# PICkit_2.net
KiCad netlist of a schematic drawn in Altium Designer
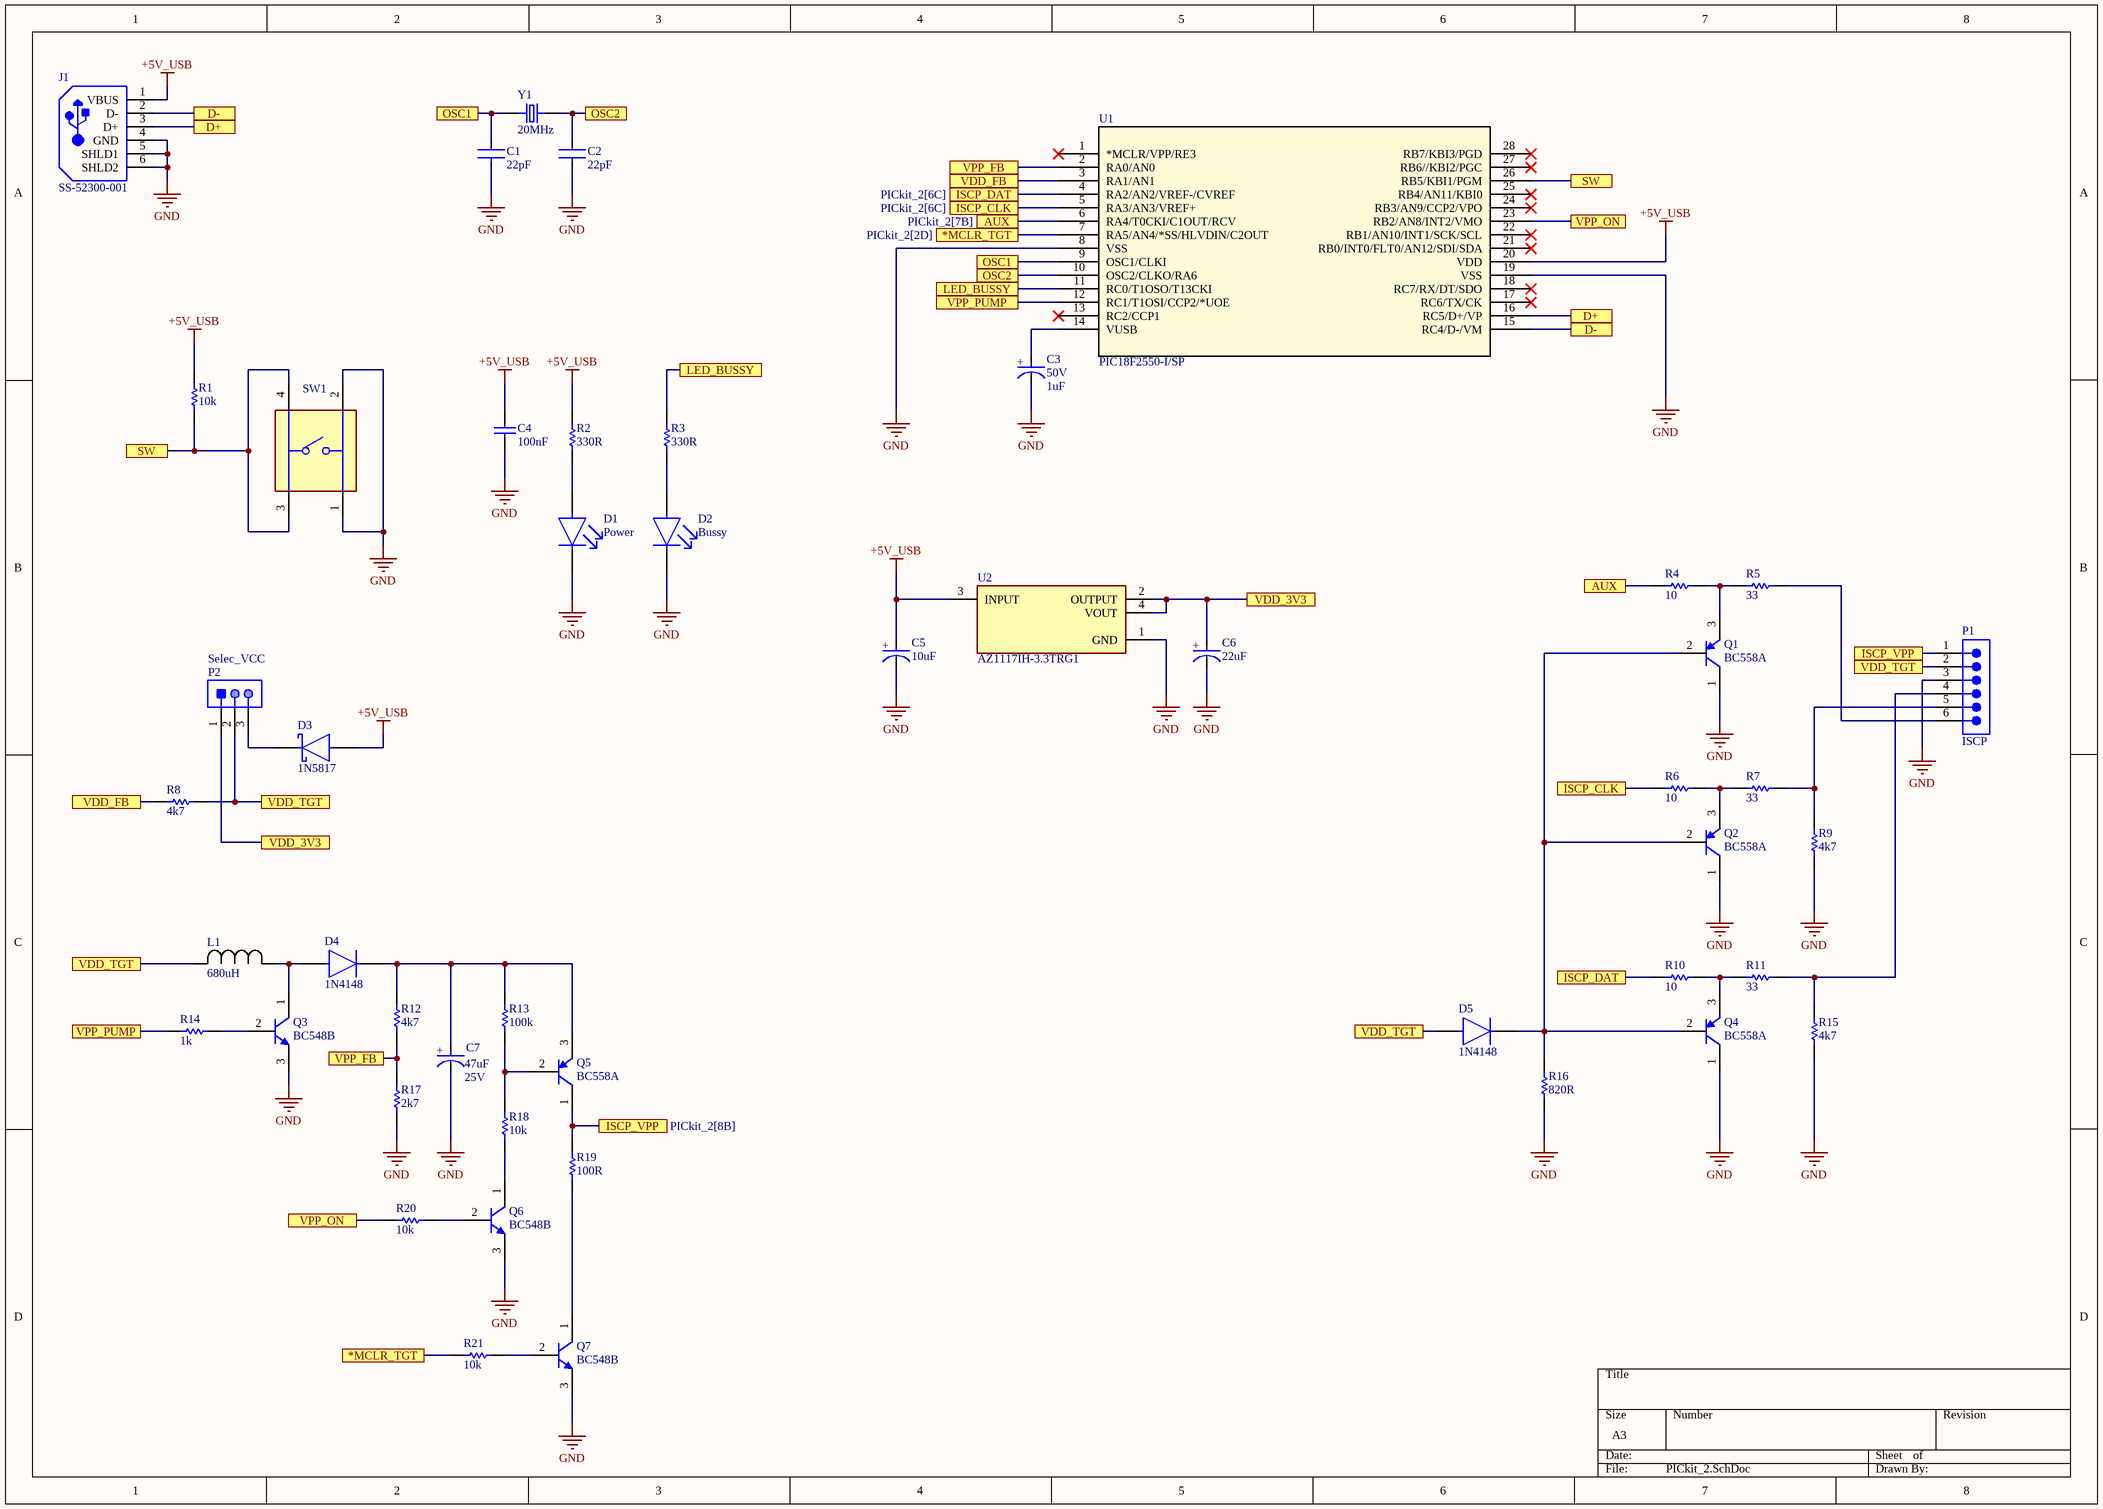
[diagram p0: PICkit_2.SchDoc]

(export (version "E")
  (design (tool "Eeschema 10.0.6"))
  (components
    (comp (ref "C1")
      (value "RCE5C1H220J0K1H03B")
      (footprint "FP-RCE0K1-MFG")
      (description "Cap Ceramic 22pF 50V C0G ±5% Radial 5mm +125°C Automotive Bulk")
      (fields
        (field (name "TOLERANCE") "5%")
        (field (name "CAPACITANCE") "22pF")
        (field (name "MANUFACTURER") "Murata")
      )
      (libsource (lib "Altium Content Vault") (part "b4654b650e69147ec39a6b967a45e02"))
    )
    (comp (ref "C2")
      (value "RCE5C1H220J0K1H03B")
      (footprint "FP-RCE0K1-MFG")
      (description "Cap Ceramic 22pF 50V C0G ±5% Radial 5mm +125°C Automotive Bulk")
      (fields
        (field (name "TOLERANCE") "5%")
        (field (name "CAPACITANCE") "22pF")
        (field (name "MANUFACTURER") "Murata")
      )
      (libsource (lib "Altium Content Vault") (part "b4654b650e69147ec39a6b967a45e02"))
    )
    (comp (ref "C3")
      (value "EEUHD1H1R0")
      (footprint "FP-RAD-TH-D_5_0_5-L_11_1-MFG")
      (description "Aluminum Electrolytic Capacitors (Radial Lead Type) AEC-Q200 Qualified 1uF ±20% 50V")
      (fields
        (field (name "VOLTAGE") "50V")
        (field (name "TOLERANCE") "20%")
        (field (name "CAPACITANCE") "1uF")
      )
      (libsource (lib "Altium Content Vault") (part "a00bbbee19879c290e62620ae7e47b1"))
    )
    (comp (ref "C4")
      (value "C320C104K5R5TA")
      (footprint "CAPR51-254-508X318X736")
      (fields
        (field (name "MANUFACTURER") "KEMET")
        (field (name "TOLERANCE") "10%")
        (field (name "CAPACITANCE") "100nF")
        (field (name "VOLTAGE") "50V")
      )
      (libsource (lib "Altium Content Vault") (part "CAP-NP-2"))
    )
    (comp (ref "C5")
      (value "ECA1HHG100I")
      (footprint "FP-RAD-TH-D_5_0_5-L_11_1-MFG")
      (description "Aluminum Electrolytic Capacitors (Radial Lead Type) AEC-Q200 Qualified 10uF ±20% 50V")
      (fields
        (field (name "CAPACITANCE") "10uF")
        (field (name "TOLERANCE") "20%")
        (field (name "MANUFACTURER") "Panasonic")
      )
      (libsource (lib "Altium Content Vault") (part "a00bbbee19879c290e62620ae7e47b1"))
    )
    (comp (ref "C6")
      (value "ECA1CM220B")
      (footprint "FP-RAD-TH-D_5_0_5-L_11_1-MFG")
      (description "Aluminum Electrolytic Capacitors (Radial Lead Type) 22uF ±20% 16V")
      (fields
        (field (name "TOLERANCE") "20%")
        (field (name "CAPACITANCE") "22uF")
        (field (name "MANUFACTURER") "Panasonic")
      )
      (libsource (lib "Altium Content Vault") (part "a00bbbee19879c290e62620ae7e47b1"))
    )
    (comp (ref "C7")
      (value "EEUFM1E470")
      (footprint "FP-RAD-TH-D_5_0_5-L_11_1-MFG")
      (description "Aluminum Electrolytic Capacitors (Radial Lead Type) 47uF ±20% 25V")
      (fields
        (field (name "VOLTAGE RATING") "25V")
        (field (name "CAPACITANCE") "47uF")
        (field (name "TOLERANCE") "20%")
        (field (name "VOLTAGE") "25V")
      )
      (libsource (lib "Altium Content Vault") (part "a00bbbee19879c290e62620ae7e47b1"))
    )
    (comp (ref "D1")
      (value "HLMP-1719")
      (footprint "FP-HLMP-1719-MFG")
      (description "LED YELLOW DIFFUSED T-1 T/H")
      (fields
        (field (name "MANUFACTURER") "Broadcom")
        (field (name "COLOUR") "Power")
        (field (name "OCTOPART") "https://octopart.com/hlmp-1719-broadcom-71130405")
      )
      (libsource (lib "Altium Content Vault") (part "8706943c75ba83719d021d2fdc84c58"))
    )
    (comp (ref "D2")
      (value "HLMP-1719")
      (footprint "FP-HLMP-1719-MFG")
      (description "LED YELLOW DIFFUSED T-1 T/H")
      (fields
        (field (name "MANUFACTURER") "Broadcom")
        (field (name "COLOUR") "Bussy")
        (field (name "OCTOPART") "https://octopart.com/hlmp-1719-broadcom-71130405")
      )
      (libsource (lib "Altium Content Vault") (part "8706943c75ba83719d021d2fdc84c58"))
    )
    (comp (ref "D3")
      (value "1N5817")
      (footprint "FP-DO-41-MFG")
      (description "DIODE SCHOTTKY 20V 1A DO41")
      (fields
        (field (name "MANUFACTURER") "STMicroelectronics")
        (field (name "MANUFACTURER PART NUMBER") "1N5817")
      )
      (libsource (lib "Altium Content Vault") (part "1d6ec82d83fb6aee721767c19dac4b9"))
    )
    (comp (ref "D4")
      (value "1N4148")
      (footprint "FP-6_560-5004_12-4-MFG")
      (description "DIODE GEN PURP 75V 300MA DO35")
      (fields
        (field (name "MANUFACTURER") "Vishay Vitramon")
        (field (name "MANUFACTURER PART NUMBER") "1N4148TR")
      )
      (libsource (lib "Altium Content Vault") (part "d7152d700b627762746794eb795d46e"))
    )
    (comp (ref "D5")
      (value "1N4148")
      (footprint "FP-6_560-5004_12-4-MFG")
      (description "DIODE GEN PURP 75V 300MA DO35")
      (fields
        (field (name "MANUFACTURER") "Vishay Vitramon")
        (field (name "MANUFACTURER PART NUMBER") "1N4148TR")
      )
      (libsource (lib "Altium Content Vault") (part "d7152d700b627762746794eb795d46e"))
    )
    (comp (ref "J1")
      (value "SS-52300-001")
      (footprint "SS-52300-001")
      (description "Usb 2.0 Right Angle Receptacle Type B; Usb 2.0 Right Angle Receptacle Type B")
      (fields (field (name "MANUFACTURER") "Bel"))
      (libsource (lib "SS-52300-001") (part "SS-52300-001"))
    )
    (comp (ref "L1")
      (value "78F681J-RC")
      (footprint "IND_BOURNS_78F")
      (description "Ind RF Choke Bobbin Core 680uH 5% 790KHz 60Q-Factor Ferrite 68mA AXL Bag")
      (fields
        (field (name "MANUFACTURER") "Bourns")
        (field (name "TOLERANCE") "5%")
        (field (name "INDUCTANCE") "680uH")
        (field (name "COPYRIGHT") "Copyright (C) 2023 Ultra Librarian. All rights reserved.")
      )
      (libsource (lib "78F681J-RC") (part "78F681J-RC"))
    )
    (comp (ref "P1")
      (value "ISCP")
      (footprint "SMTC-TSW-106-08-X-S-RA")
      (fields (field (name "MANUFACTURER") "Samtec") (field (name "PARTNUMBER") "TSW-106-08-L-S-RA"))
      (libsource (lib "Altium Content Vault") (part "SMTC-TSW-106-X-X-S-X"))
    )
    (comp (ref "P2")
      (value "22-28-4033")
      (footprint "MOLX-22-28-4033_V")
      (description "Male Header, Pitch 2.54 mm, 1 x 3 Position, Height 8.38 mm, Tail Length 3.18 mm, RoHS, Bulk")
      (fields (field (name "MANUFACTURER") "Molex") (field (name "ACTION") "Selec_VCC"))
      (libsource (lib "Altium Content Vault") (part "CN-1P-M-R3"))
    )
    (comp (ref "Q1")
      (value "BC558A")
      (footprint "ONSC-TO-92-3-29-11_AM_BL")
      (description "Amplifier Transistor, PNP Silicon, 3-Pin TO-92, Pb-Free, Tape and Reel")
      (fields (field (name "PARTNUMBER") "BC558BRLG") (field (name "MANUFACTURER") "On Semiconductor"))
      (libsource (lib "Altium Content Vault") (part "ONSC-PNP-C1B2E3-3"))
    )
    (comp (ref "Q2")
      (value "BC558A")
      (footprint "ONSC-TO-92-3-29-11_AM_BL")
      (description "Amplifier Transistor, PNP Silicon, 3-Pin TO-92, Pb-Free, Tape and Reel")
      (fields (field (name "PARTNUMBER") "BC558BRLG") (field (name "MANUFACTURER") "On Semiconductor"))
      (libsource (lib "Altium Content Vault") (part "ONSC-PNP-C1B2E3-3"))
    )
    (comp (ref "Q3")
      (value "BC548B")
      (footprint "ONSC-TO-92-3-29-11")
      (description "Amplifier Transistor, NPN Silicon, 3-Pin TO-92, Bulk Box")
      (fields (field (name "MANUFACTURER") "On Semiconductor"))
      (libsource (lib "Altium Content Vault") (part "ONSC-NPN-C1B2E3-3"))
    )
    (comp (ref "Q4")
      (value "BC558A")
      (footprint "ONSC-TO-92-3-29-11_AM_BL")
      (description "Amplifier Transistor, PNP Silicon, 3-Pin TO-92, Pb-Free, Tape and Reel")
      (fields (field (name "PARTNUMBER") "BC558BRLG") (field (name "MANUFACTURER") "On Semiconductor"))
      (libsource (lib "Altium Content Vault") (part "ONSC-PNP-C1B2E3-3"))
    )
    (comp (ref "Q5")
      (value "BC558A")
      (footprint "ONSC-TO-92-3-29-11_AM_BL")
      (description "Amplifier Transistor, PNP Silicon, 3-Pin TO-92, Pb-Free, Tape and Reel")
      (fields (field (name "PARTNUMBER") "BC558BRLG") (field (name "MANUFACTURER") "On Semiconductor"))
      (libsource (lib "Altium Content Vault") (part "ONSC-PNP-C1B2E3-3"))
    )
    (comp (ref "Q6")
      (value "BC548B")
      (footprint "ONSC-TO-92-3-29-11")
      (description "Amplifier Transistor, NPN Silicon, 3-Pin TO-92, Bulk Box")
      (fields (field (name "MANUFACTURER") "On Semiconductor"))
      (libsource (lib "Altium Content Vault") (part "ONSC-NPN-C1B2E3-3"))
    )
    (comp (ref "Q7")
      (value "BC548B")
      (footprint "ONSC-TO-92-3-29-11")
      (description "Amplifier Transistor, NPN Silicon, 3-Pin TO-92, Bulk Box")
      (fields (field (name "MANUFACTURER") "On Semiconductor"))
      (libsource (lib "Altium Content Vault") (part "ONSC-NPN-C1B2E3-3"))
    )
    (comp (ref "R1")
      (value "CF14JT10K0")
      (footprint "CF14JT10K0")
      (description "Res Carbon Film 10K Ohm 5% 0.25W(1/4W) -500ppm/ to¦")
      (fields
        (field (name "MANUFACTURER") "Stackpole Electronics")
        (field (name "TOLERANCE") "5%")
        (field (name "RESISTANCE") "10k")
      )
      (libsource (lib "RES_10K_THT") (part "CF14JT10K0"))
    )
    (comp (ref "R2")
      (value "1-1623728-6")
      (footprint "CF14JT10K0")
      (description "Res Wirewound 330 Ohm 5% 11W ±200ppm/C Ceramic AXL Box/Loose")
      (fields
        (field (name "MANUFACTURER") "TE Connectivity")
        (field (name "RESISTANCE") "330R")
        (field (name "TOLERANCE") "5%")
      )
      (libsource (lib "RES_10K_THT") (part "CF14JT10K0"))
    )
    (comp (ref "R3")
      (value "1-1623728-6")
      (footprint "CF14JT10K0")
      (description "Res Wirewound 330 Ohm 5% 11W ±200ppm/C Ceramic AXL Box/Loose")
      (fields
        (field (name "MANUFACTURER") "TE Connectivity")
        (field (name "RESISTANCE") "330R")
        (field (name "TOLERANCE") "5%")
      )
      (libsource (lib "RES_10K_THT") (part "CF14JT10K0"))
    )
    (comp (ref "R4")
      (value "MFR-25FBF52-1K")
      (footprint "RESA60-630X240")
      (description "Axial Resistor, 1 KOhm, +/- 1%, 250 mW, -55 to 155 degC, 2-Pin THD, RoHS, Bulk")
      (fields
        (field (name "TOLERANCE") "1%")
        (field (name "RESISTANCE") "10")
        (field (name "MANUFACTURER") "Yageo")
      )
      (libsource (lib "Altium Content Vault") (part "RES-2"))
    )
    (comp (ref "R5")
      (value "MFR-25FBF52-1K")
      (footprint "RESA60-630X240")
      (description "Axial Resistor, 1 KOhm, +/- 1%, 250 mW, -55 to 155 degC, 2-Pin THD, RoHS, Bulk")
      (fields
        (field (name "TOLERANCE") "1%")
        (field (name "RESISTANCE") "33")
        (field (name "MANUFACTURER") "Yageo")
      )
      (libsource (lib "Altium Content Vault") (part "RES-2"))
    )
    (comp (ref "R6")
      (value "MFR-25FBF52-1K")
      (footprint "RESA60-630X240")
      (description "Axial Resistor, 1 KOhm, +/- 1%, 250 mW, -55 to 155 degC, 2-Pin THD, RoHS, Bulk")
      (fields
        (field (name "TOLERANCE") "1%")
        (field (name "RESISTANCE") "10")
        (field (name "MANUFACTURER") "Yageo")
      )
      (libsource (lib "Altium Content Vault") (part "RES-2"))
    )
    (comp (ref "R7")
      (value "MFR-25FBF52-1K")
      (footprint "RESA60-630X240")
      (description "Axial Resistor, 1 KOhm, +/- 1%, 250 mW, -55 to 155 degC, 2-Pin THD, RoHS, Bulk")
      (fields
        (field (name "TOLERANCE") "1%")
        (field (name "RESISTANCE") "33")
        (field (name "MANUFACTURER") "Yageo")
      )
      (libsource (lib "Altium Content Vault") (part "RES-2"))
    )
    (comp (ref "R8")
      (value "~")
      (footprint "CF14JT10K0")
      (description "Res Thin Film 4.7K Ohm 1% 2/5W ±50ppm/°C Conformal AXL Thru-Hole Ammo Pack")
      (fields
        (field (name "MANUFACTURER") "Vishay Beyschlag")
        (field (name "MANUFACTURER PART NUMBER") "MBA02040C4701FC100")
        (field (name "RESISTANCE") "4k7")
      )
      (libsource (lib "RES_10K_THT") (part "CF14JT10K0"))
    )
    (comp (ref "R9")
      (value "~")
      (footprint "CF14JT10K0")
      (description "Res Thin Film 4.7K Ohm 1% 2/5W ±50ppm/°C Conformal AXL Thru-Hole Ammo Pack")
      (fields
        (field (name "MANUFACTURER") "Vishay Beyschlag")
        (field (name "MANUFACTURER PART NUMBER") "MBA02040C4701FC100")
        (field (name "RESISTANCE") "4k7")
      )
      (libsource (lib "RES_10K_THT") (part "CF14JT10K0"))
    )
    (comp (ref "R10")
      (value "MFR-25FBF52-1K")
      (footprint "RESA60-630X240")
      (description "Axial Resistor, 1 KOhm, +/- 1%, 250 mW, -55 to 155 degC, 2-Pin THD, RoHS, Bulk")
      (fields
        (field (name "TOLERANCE") "1%")
        (field (name "RESISTANCE") "10")
        (field (name "MANUFACTURER") "Yageo")
      )
      (libsource (lib "Altium Content Vault") (part "RES-2"))
    )
    (comp (ref "R11")
      (value "MFR-25FBF52-1K")
      (footprint "RESA60-630X240")
      (description "Axial Resistor, 1 KOhm, +/- 1%, 250 mW, -55 to 155 degC, 2-Pin THD, RoHS, Bulk")
      (fields
        (field (name "TOLERANCE") "1%")
        (field (name "RESISTANCE") "33")
        (field (name "MANUFACTURER") "Yageo")
      )
      (libsource (lib "Altium Content Vault") (part "RES-2"))
    )
    (comp (ref "R12")
      (value "~")
      (footprint "CF14JT10K0")
      (description "Res Thin Film 4.7K Ohm 1% 2/5W ±50ppm/°C Conformal AXL Thru-Hole Ammo Pack")
      (fields
        (field (name "MANUFACTURER") "Vishay Beyschlag")
        (field (name "MANUFACTURER PART NUMBER") "MBA02040C4701FC100")
        (field (name "RESISTANCE") "4k7")
      )
      (libsource (lib "RES_10K_THT") (part "CF14JT10K0"))
    )
    (comp (ref "R13")
      (value "MFR-25FBF52-1K")
      (footprint "RESA60-630X240")
      (description "Axial Resistor, 1 KOhm, +/- 1%, 250 mW, -55 to 155 degC, 2-Pin THD, RoHS, Bulk")
      (fields
        (field (name "TOLERANCE") "1%")
        (field (name "RESISTANCE") "100k")
        (field (name "MANUFACTURER") "Yageo")
      )
      (libsource (lib "Altium Content Vault") (part "RES-2"))
    )
    (comp (ref "R14")
      (value "MFR-25FBF52-1K")
      (footprint "RESA60-630X240")
      (description "Axial Resistor, 1 KOhm, +/- 1%, 250 mW, -55 to 155 degC, 2-Pin THD, RoHS, Bulk")
      (fields
        (field (name "TOLERANCE") "1%")
        (field (name "RESISTANCE") "1k")
        (field (name "MANUFACTURER") "Yageo")
      )
      (libsource (lib "Altium Content Vault") (part "RES-2"))
    )
    (comp (ref "R15")
      (value "~")
      (footprint "CF14JT10K0")
      (description "Res Thin Film 4.7K Ohm 1% 2/5W ±50ppm/°C Conformal AXL Thru-Hole Ammo Pack")
      (fields
        (field (name "MANUFACTURER") "Vishay Beyschlag")
        (field (name "MANUFACTURER PART NUMBER") "MBA02040C4701FC100")
        (field (name "RESISTANCE") "4k7")
      )
      (libsource (lib "RES_10K_THT") (part "CF14JT10K0"))
    )
    (comp (ref "R16")
      (value "MFR-25FBF52-1K")
      (footprint "RESA60-630X240")
      (description "Axial Resistor, 1 KOhm, +/- 1%, 250 mW, -55 to 155 degC, 2-Pin THD, RoHS, Bulk")
      (fields
        (field (name "TOLERANCE") "1%")
        (field (name "RESISTANCE") "820R")
        (field (name "MANUFACTURER") "Yageo")
      )
      (libsource (lib "Altium Content Vault") (part "RES-2"))
    )
    (comp (ref "R17")
      (value "MFR-25FBF52-1K")
      (footprint "RESA60-630X240")
      (description "Axial Resistor, 1 KOhm, +/- 1%, 250 mW, -55 to 155 degC, 2-Pin THD, RoHS, Bulk")
      (fields
        (field (name "TOLERANCE") "1%")
        (field (name "RESISTANCE") "2k7")
        (field (name "MANUFACTURER") "Yageo")
      )
      (libsource (lib "Altium Content Vault") (part "RES-2"))
    )
    (comp (ref "R18")
      (value "MFR-25FBF52-1K")
      (footprint "RESA60-630X240")
      (description "Axial Resistor, 1 KOhm, +/- 1%, 250 mW, -55 to 155 degC, 2-Pin THD, RoHS, Bulk")
      (fields
        (field (name "TOLERANCE") "1%")
        (field (name "RESISTANCE") "10k")
        (field (name "MANUFACTURER") "Yageo")
      )
      (libsource (lib "Altium Content Vault") (part "RES-2"))
    )
    (comp (ref "R19")
      (value "MFR-25FBF52-1K")
      (footprint "RESA60-630X240")
      (description "Axial Resistor, 1 KOhm, +/- 1%, 250 mW, -55 to 155 degC, 2-Pin THD, RoHS, Bulk")
      (fields
        (field (name "TOLERANCE") "1%")
        (field (name "RESISTANCE") "100R")
        (field (name "MANUFACTURER") "Yageo")
      )
      (libsource (lib "Altium Content Vault") (part "RES-2"))
    )
    (comp (ref "R20")
      (value "MFR-25FBF52-1K")
      (footprint "RESA60-630X240")
      (description "Axial Resistor, 1 KOhm, +/- 1%, 250 mW, -55 to 155 degC, 2-Pin THD, RoHS, Bulk")
      (fields
        (field (name "TOLERANCE") "1%")
        (field (name "RESISTANCE") "10k")
        (field (name "MANUFACTURER") "Yageo")
      )
      (libsource (lib "Altium Content Vault") (part "RES-2"))
    )
    (comp (ref "R21")
      (value "MFR-25FBF52-1K")
      (footprint "RESA60-630X240")
      (description "Axial Resistor, 1 KOhm, +/- 1%, 250 mW, -55 to 155 degC, 2-Pin THD, RoHS, Bulk")
      (fields
        (field (name "TOLERANCE") "1%")
        (field (name "RESISTANCE") "10k")
        (field (name "MANUFACTURER") "Yageo")
      )
      (libsource (lib "Altium Content Vault") (part "RES-2"))
    )
    (comp (ref "SW1")
      (value "TS02-66-60-BK-100-LCR-D")
      (footprint "SW_TS02-66-60-BK-100-LCR-D")
      (description "6 x 6 mm, 4.3 ~ 17 mm Actuator Height, 100 ~ 260 gf, Through Hole, SPST, Tactile Switch")
      (fields (field (name "MANUFACTURER") "CUI Devices"))
      (libsource (lib "TS02-66-60-BK-100-LCR-D") (part "TS02-66-60-BK-100-LCR-D"))
    )
    (comp (ref "U1")
      (value "PIC18F2550-I/SP")
      (footprint "PIC18F2550-I/SP")
      (description "Microcontroller, 32 Kb Flash, 2048 Ram, 256 EEPROM, 24 I/o, SPDIP-28")
      (fields
        (field (name "MANUFACTURER") "Microchip")
        (field (name "COPYRIGHT") "Copyright (C) 2023 Ultra Librarian. All rights reserved.")
      )
      (libsource (lib "PIC18F2550-I-SP") (part "PIC18F2550-I/SP"))
    )
    (comp (ref "U2")
      (value "AZ1117IH-3.3TRG1")
      (footprint "FP-SOT223-IPC_B")
      (description "IC REG LINEAR 3.3V 1A SOT223")
      (fields (field (name "MANUFACTURER") "Diodes"))
      (libsource (lib "Altium Content Vault") (part "3c8a0cc3f7d1fafcf032f21e1bb5f65"))
    )
    (comp (ref "Y1")
      (value "ECS-200-20-4X")
      (footprint "XTAL_ECS-200-20-4X")
      (description "Crystal 20MHz ±30ppm (Tol) ±50ppm (Stability) 20pF FUND 30Ohm 2-Pin HC-49/USX Thru-Hole Bulk")
      (fields
        (field (name "MANUFACTURER") "ECS International")
        (field (name "TOLERANCE") "30ppm")
        (field (name "FREQUENCY") "20MHz")
      )
      (libsource (lib "ECS-200-20-4X") (part "ECS-200-20-4X"))
    )
  )
  (nets
    (net (code "1") (name "+5V_USB") (class "Default")
      (node (ref "C4") (pin "1") (pinfunction "1_1") (pintype "passive"))
      (node (ref "C5") (pin "2") (pinfunction "A_2") (pintype "passive"))
      (node (ref "D3") (pin "2") (pinfunction "A_2") (pintype "passive"))
      (node (ref "J1") (pin "1") (pinfunction "VBUS_1") (pintype "passive"))
      (node (ref "R1") (pin "2") (pinfunction "2_2") (pintype "passive"))
      (node (ref "R2") (pin "1") (pinfunction "1_1") (pintype "passive"))
      (node (ref "U1") (pin "20") (pinfunction "VDD_20") (pintype "passive"))
      (node (ref "U2") (pin "3") (pinfunction "INPUT_3") (pintype "power_in"))
    )
    (net (code "2") (name "/*MCLR_TGT") (class "Default")
      (node (ref "R21") (pin "2") (pinfunction "2_2") (pintype "passive"))
      (node (ref "U1") (pin "7") (pinfunction "RA5/AN4/*SS/HLVDIN/C2OUT_7") (pintype "passive"))
    )
    (net (code "3") (name "/AUX") (class "Default")
      (node (ref "R4") (pin "2") (pinfunction "2_2") (pintype "passive"))
      (node (ref "U1") (pin "6") (pinfunction "RA4/T0CKI/C1OUT/RCV_6") (pintype "passive"))
    )
    (net (code "4") (name "/D+") (class "Default")
      (node (ref "J1") (pin "3") (pinfunction "D+_3") (pintype "passive"))
      (node (ref "U1") (pin "16") (pinfunction "RC5/D+/VP_16") (pintype "passive"))
    )
    (net (code "5") (name "/D-") (class "Default")
      (node (ref "J1") (pin "2") (pinfunction "D-_2") (pintype "passive"))
      (node (ref "U1") (pin "15") (pinfunction "RC4/D-/VM_15") (pintype "passive"))
    )
    (net (code "6") (name "/ISCP_CLK") (class "Default")
      (node (ref "R6") (pin "2") (pinfunction "2_2") (pintype "passive"))
      (node (ref "U1") (pin "5") (pinfunction "RA3/AN3/VREF+_5") (pintype "passive"))
    )
    (net (code "7") (name "/ISCP_DAT") (class "Default")
      (node (ref "R10") (pin "2") (pinfunction "2_2") (pintype "passive"))
      (node (ref "U1") (pin "4") (pinfunction "RA2/AN2/VREF-/CVREF_4") (pintype "passive"))
    )
    (net (code "8") (name "/ISCP_VPP") (class "Default")
      (node (ref "P1") (pin "1") (pinfunction "1_1") (pintype "passive"))
      (node (ref "Q5") (pin "1") (pinfunction "C_1") (pintype "passive"))
      (node (ref "R19") (pin "2") (pinfunction "2_2") (pintype "passive"))
    )
    (net (code "9") (name "/LED_BUSSY") (class "Default")
      (node (ref "R3") (pin "1") (pinfunction "1_1") (pintype "passive"))
      (node (ref "U1") (pin "11") (pinfunction "RC0/T1OSO/T13CKI_11") (pintype "passive"))
    )
    (net (code "10") (name "/OSC1") (class "Default")
      (node (ref "C1") (pin "2") (pinfunction "2_2") (pintype "passive"))
      (node (ref "U1") (pin "9") (pinfunction "OSC1/CLKI_9") (pintype "passive"))
      (node (ref "Y1") (pin "1") (pinfunction "1_1") (pintype "passive"))
    )
    (net (code "11") (name "/OSC2") (class "Default")
      (node (ref "C2") (pin "2") (pinfunction "2_2") (pintype "passive"))
      (node (ref "U1") (pin "10") (pinfunction "OSC2/CLKO/RA6_10") (pintype "passive"))
      (node (ref "Y1") (pin "2") (pinfunction "2_2") (pintype "passive"))
    )
    (net (code "12") (name "/SW") (class "Default")
      (node (ref "R1") (pin "1") (pinfunction "1_1") (pintype "passive"))
      (node (ref "SW1") (pin "3") (pinfunction "3_3") (pintype "passive"))
      (node (ref "SW1") (pin "4") (pinfunction "4_4") (pintype "passive"))
      (node (ref "U1") (pin "26") (pinfunction "RB5/KBI1/PGM_26") (pintype "passive"))
    )
    (net (code "13") (name "/VDD_3V3") (class "Default")
      (node (ref "C6") (pin "2") (pinfunction "A_2") (pintype "passive"))
      (node (ref "P2") (pin "1") (pinfunction "1_1") (pintype "passive"))
      (node (ref "U2") (pin "2") (pinfunction "OUTPUT_2") (pintype "power_in"))
      (node (ref "U2") (pin "4") (pinfunction "VOUT_4") (pintype "power_in"))
    )
    (net (code "14") (name "/VDD_FB") (class "Default")
      (node (ref "R8") (pin "2") (pinfunction "2_2") (pintype "passive"))
      (node (ref "U1") (pin "3") (pinfunction "RA1/AN1_3") (pintype "passive"))
    )
    (net (code "15") (name "/VDD_TGT") (class "Default")
      (node (ref "D5") (pin "2") (pinfunction "A_2") (pintype "passive"))
      (node (ref "L1") (pin "2") (pinfunction "2_2") (pintype "passive"))
      (node (ref "P1") (pin "2") (pinfunction "2_2") (pintype "passive"))
      (node (ref "P2") (pin "2") (pinfunction "2_2") (pintype "passive"))
      (node (ref "R8") (pin "1") (pinfunction "1_1") (pintype "passive"))
    )
    (net (code "16") (name "/VPP_FB") (class "Default")
      (node (ref "R12") (pin "2") (pinfunction "2_2") (pintype "passive"))
      (node (ref "R17") (pin "2") (pinfunction "2_2") (pintype "passive"))
      (node (ref "U1") (pin "2") (pinfunction "RA0/AN0_2") (pintype "passive"))
    )
    (net (code "17") (name "/VPP_ON") (class "Default")
      (node (ref "R20") (pin "2") (pinfunction "2_2") (pintype "passive"))
      (node (ref "U1") (pin "23") (pinfunction "RB2/AN8/INT2/VMO_23") (pintype "passive"))
    )
    (net (code "18") (name "/VPP_PUMP") (class "Default")
      (node (ref "R14") (pin "1") (pinfunction "1_1") (pintype "passive"))
      (node (ref "U1") (pin "12") (pinfunction "RC1/T1OSI/CCP2/*UOE_12") (pintype "passive"))
    )
    (net (code "19") (name "GND") (class "Default")
      (node (ref "C1") (pin "1") (pinfunction "1_1") (pintype "passive"))
      (node (ref "C2") (pin "1") (pinfunction "1_1") (pintype "passive"))
      (node (ref "C3") (pin "1") (pinfunction "C_1") (pintype "passive"))
      (node (ref "C4") (pin "2") (pinfunction "2_2") (pintype "passive"))
      (node (ref "C5") (pin "1") (pinfunction "C_1") (pintype "passive"))
      (node (ref "C6") (pin "1") (pinfunction "C_1") (pintype "passive"))
      (node (ref "C7") (pin "1") (pinfunction "C_1") (pintype "passive"))
      (node (ref "D1") (pin "1") (pinfunction "C_1") (pintype "passive"))
      (node (ref "D2") (pin "1") (pinfunction "C_1") (pintype "passive"))
      (node (ref "J1") (pin "4") (pinfunction "GND_4") (pintype "passive"))
      (node (ref "J1") (pin "5") (pinfunction "SHLD1_5") (pintype "passive"))
      (node (ref "J1") (pin "6") (pinfunction "SHLD2_6") (pintype "passive"))
      (node (ref "P1") (pin "3") (pinfunction "3_3") (pintype "passive"))
      (node (ref "Q1") (pin "1") (pinfunction "C_1") (pintype "passive"))
      (node (ref "Q2") (pin "1") (pinfunction "C_1") (pintype "passive"))
      (node (ref "Q3") (pin "3") (pinfunction "E_3") (pintype "passive"))
      (node (ref "Q4") (pin "1") (pinfunction "C_1") (pintype "passive"))
      (node (ref "Q6") (pin "3") (pinfunction "E_3") (pintype "passive"))
      (node (ref "Q7") (pin "3") (pinfunction "E_3") (pintype "passive"))
      (node (ref "R15") (pin "2") (pinfunction "2_2") (pintype "passive"))
      (node (ref "R16") (pin "1") (pinfunction "1_1") (pintype "passive"))
      (node (ref "R17") (pin "1") (pinfunction "1_1") (pintype "passive"))
      (node (ref "R9") (pin "2") (pinfunction "2_2") (pintype "passive"))
      (node (ref "SW1") (pin "1") (pinfunction "1_1") (pintype "passive"))
      (node (ref "SW1") (pin "2") (pinfunction "2_2") (pintype "passive"))
      (node (ref "U1") (pin "19") (pinfunction "VSS_19") (pintype "passive"))
      (node (ref "U1") (pin "8") (pinfunction "VSS_8") (pintype "passive"))
      (node (ref "U2") (pin "1") (pinfunction "GND_1") (pintype "power_in"))
    )
    (net (code "20") (name "Net-(C3-A)") (class "Default")
      (node (ref "C3") (pin "2") (pinfunction "A_2") (pintype "passive"))
      (node (ref "U1") (pin "14") (pinfunction "VUSB_14") (pintype "passive"))
    )
    (net (code "21") (name "Net-(C7-A)") (class "Default")
      (node (ref "C7") (pin "2") (pinfunction "A_2") (pintype "passive"))
      (node (ref "D4") (pin "1") (pinfunction "C_1") (pintype "passive"))
      (node (ref "Q5") (pin "3") (pinfunction "E_3") (pintype "passive"))
      (node (ref "R12") (pin "1") (pinfunction "1_1") (pintype "passive"))
      (node (ref "R13") (pin "2") (pinfunction "2_2") (pintype "passive"))
    )
    (net (code "22") (name "Net-(D1-A)") (class "Default")
      (node (ref "D1") (pin "2") (pinfunction "A_2") (pintype "passive"))
      (node (ref "R2") (pin "2") (pinfunction "2_2") (pintype "passive"))
    )
    (net (code "23") (name "Net-(D2-A)") (class "Default")
      (node (ref "D2") (pin "2") (pinfunction "A_2") (pintype "passive"))
      (node (ref "R3") (pin "2") (pinfunction "2_2") (pintype "passive"))
    )
    (net (code "24") (name "Net-(D3-C)") (class "Default")
      (node (ref "D3") (pin "1") (pinfunction "C_1") (pintype "passive"))
      (node (ref "P2") (pin "3") (pinfunction "3_3") (pintype "passive"))
    )
    (net (code "25") (name "Net-(D4-A)") (class "Default")
      (node (ref "D4") (pin "2") (pinfunction "A_2") (pintype "passive"))
      (node (ref "L1") (pin "1") (pinfunction "1_1") (pintype "passive"))
      (node (ref "Q3") (pin "1") (pinfunction "C_1") (pintype "passive"))
    )
    (net (code "26") (name "Net-(D5-C)") (class "Default")
      (node (ref "D5") (pin "1") (pinfunction "C_1") (pintype "passive"))
      (node (ref "Q1") (pin "2") (pinfunction "B_2") (pintype "passive"))
      (node (ref "Q2") (pin "2") (pinfunction "B_2") (pintype "passive"))
      (node (ref "Q4") (pin "2") (pinfunction "B_2") (pintype "passive"))
      (node (ref "R16") (pin "2") (pinfunction "2_2") (pintype "passive"))
    )
    (net (code "27") (name "Net-(P1-Pad4)") (class "Default")
      (node (ref "P1") (pin "4") (pinfunction "4_4") (pintype "passive"))
      (node (ref "R11") (pin "1") (pinfunction "1_1") (pintype "passive"))
      (node (ref "R15") (pin "1") (pinfunction "1_1") (pintype "passive"))
    )
    (net (code "28") (name "Net-(P1-Pad5)") (class "Default")
      (node (ref "P1") (pin "5") (pinfunction "5_5") (pintype "passive"))
      (node (ref "R7") (pin "1") (pinfunction "1_1") (pintype "passive"))
      (node (ref "R9") (pin "1") (pinfunction "1_1") (pintype "passive"))
    )
    (net (code "29") (name "Net-(P1-Pad6)") (class "Default")
      (node (ref "P1") (pin "6") (pinfunction "6_6") (pintype "passive"))
      (node (ref "R5") (pin "1") (pinfunction "1_1") (pintype "passive"))
    )
    (net (code "30") (name "Net-(Q1-E)") (class "Default")
      (node (ref "Q1") (pin "3") (pinfunction "E_3") (pintype "passive"))
      (node (ref "R4") (pin "1") (pinfunction "1_1") (pintype "passive"))
      (node (ref "R5") (pin "2") (pinfunction "2_2") (pintype "passive"))
    )
    (net (code "31") (name "Net-(Q2-E)") (class "Default")
      (node (ref "Q2") (pin "3") (pinfunction "E_3") (pintype "passive"))
      (node (ref "R6") (pin "1") (pinfunction "1_1") (pintype "passive"))
      (node (ref "R7") (pin "2") (pinfunction "2_2") (pintype "passive"))
    )
    (net (code "32") (name "Net-(Q3-B)") (class "Default")
      (node (ref "Q3") (pin "2") (pinfunction "B_2") (pintype "passive"))
      (node (ref "R14") (pin "2") (pinfunction "2_2") (pintype "passive"))
    )
    (net (code "33") (name "Net-(Q4-E)") (class "Default")
      (node (ref "Q4") (pin "3") (pinfunction "E_3") (pintype "passive"))
      (node (ref "R10") (pin "1") (pinfunction "1_1") (pintype "passive"))
      (node (ref "R11") (pin "2") (pinfunction "2_2") (pintype "passive"))
    )
    (net (code "34") (name "Net-(Q5-B)") (class "Default")
      (node (ref "Q5") (pin "2") (pinfunction "B_2") (pintype "passive"))
      (node (ref "R13") (pin "1") (pinfunction "1_1") (pintype "passive"))
      (node (ref "R18") (pin "2") (pinfunction "2_2") (pintype "passive"))
    )
    (net (code "35") (name "Net-(Q6-B)") (class "Default")
      (node (ref "Q6") (pin "2") (pinfunction "B_2") (pintype "passive"))
      (node (ref "R20") (pin "1") (pinfunction "1_1") (pintype "passive"))
    )
    (net (code "36") (name "Net-(Q6-C)") (class "Default")
      (node (ref "Q6") (pin "1") (pinfunction "C_1") (pintype "passive"))
      (node (ref "R18") (pin "1") (pinfunction "1_1") (pintype "passive"))
    )
    (net (code "37") (name "Net-(Q7-B)") (class "Default")
      (node (ref "Q7") (pin "2") (pinfunction "B_2") (pintype "passive"))
      (node (ref "R21") (pin "1") (pinfunction "1_1") (pintype "passive"))
    )
    (net (code "38") (name "Net-(Q7-C)") (class "Default")
      (node (ref "Q7") (pin "1") (pinfunction "C_1") (pintype "passive"))
      (node (ref "R19") (pin "1") (pinfunction "1_1") (pintype "passive"))
    )
    (net (code "39") (name "unconnected-(U1-*MCLR{slash}VPP{slash}RE3-Pad1)") (class "Default")
      (node (ref "U1") (pin "1") (pinfunction "*MCLR/VPP/RE3_1") (pintype "passive+no_connect"))
    )
    (net (code "40") (name "unconnected-(U1-RB0{slash}INT0{slash}FLT0{slash}AN12{slash}SDI{slash}SDA-Pad21)") (class "Default")
      (node (ref "U1") (pin "21") (pinfunction "RB0/INT0/FLT0/AN12/SDI/SDA_21") (pintype "passive+no_connect"))
    )
    (net (code "41") (name "unconnected-(U1-RB1{slash}AN10{slash}INT1{slash}SCK{slash}SCL-Pad22)") (class "Default")
      (node (ref "U1") (pin "22") (pinfunction "RB1/AN10/INT1/SCK/SCL_22") (pintype "passive+no_connect"))
    )
    (net (code "42") (name "unconnected-(U1-RB3{slash}AN9{slash}CCP2{slash}VPO-Pad24)") (class "Default")
      (node (ref "U1") (pin "24") (pinfunction "RB3/AN9/CCP2/VPO_24") (pintype "passive+no_connect"))
    )
    (net (code "43") (name "unconnected-(U1-RB4{slash}AN11{slash}KBI0-Pad25)") (class "Default")
      (node (ref "U1") (pin "25") (pinfunction "RB4/AN11/KBI0_25") (pintype "passive+no_connect"))
    )
    (net (code "44") (name "unconnected-(U1-RB6{slash}{slash}KBI2{slash}PGC-Pad27)") (class "Default")
      (node (ref "U1") (pin "27") (pinfunction "RB6//KBI2/PGC_27") (pintype "passive+no_connect"))
    )
    (net (code "45") (name "unconnected-(U1-RB7{slash}KBI3{slash}PGD-Pad28)") (class "Default")
      (node (ref "U1") (pin "28") (pinfunction "RB7/KBI3/PGD_28") (pintype "passive+no_connect"))
    )
    (net (code "46") (name "unconnected-(U1-RC2{slash}CCP1-Pad13)") (class "Default")
      (node (ref "U1") (pin "13") (pinfunction "RC2/CCP1_13") (pintype "passive+no_connect"))
    )
    (net (code "47") (name "unconnected-(U1-RC6{slash}TX{slash}CK-Pad17)") (class "Default")
      (node (ref "U1") (pin "17") (pinfunction "RC6/TX/CK_17") (pintype "passive+no_connect"))
    )
    (net (code "48") (name "unconnected-(U1-RC7{slash}RX{slash}DT{slash}SDO-Pad18)") (class "Default")
      (node (ref "U1") (pin "18") (pinfunction "RC7/RX/DT/SDO_18") (pintype "passive+no_connect"))
    )
  )
)
